# oLoRa-part-MainMCU.net
KiCad netlist of a schematic drawn in EasyEDA
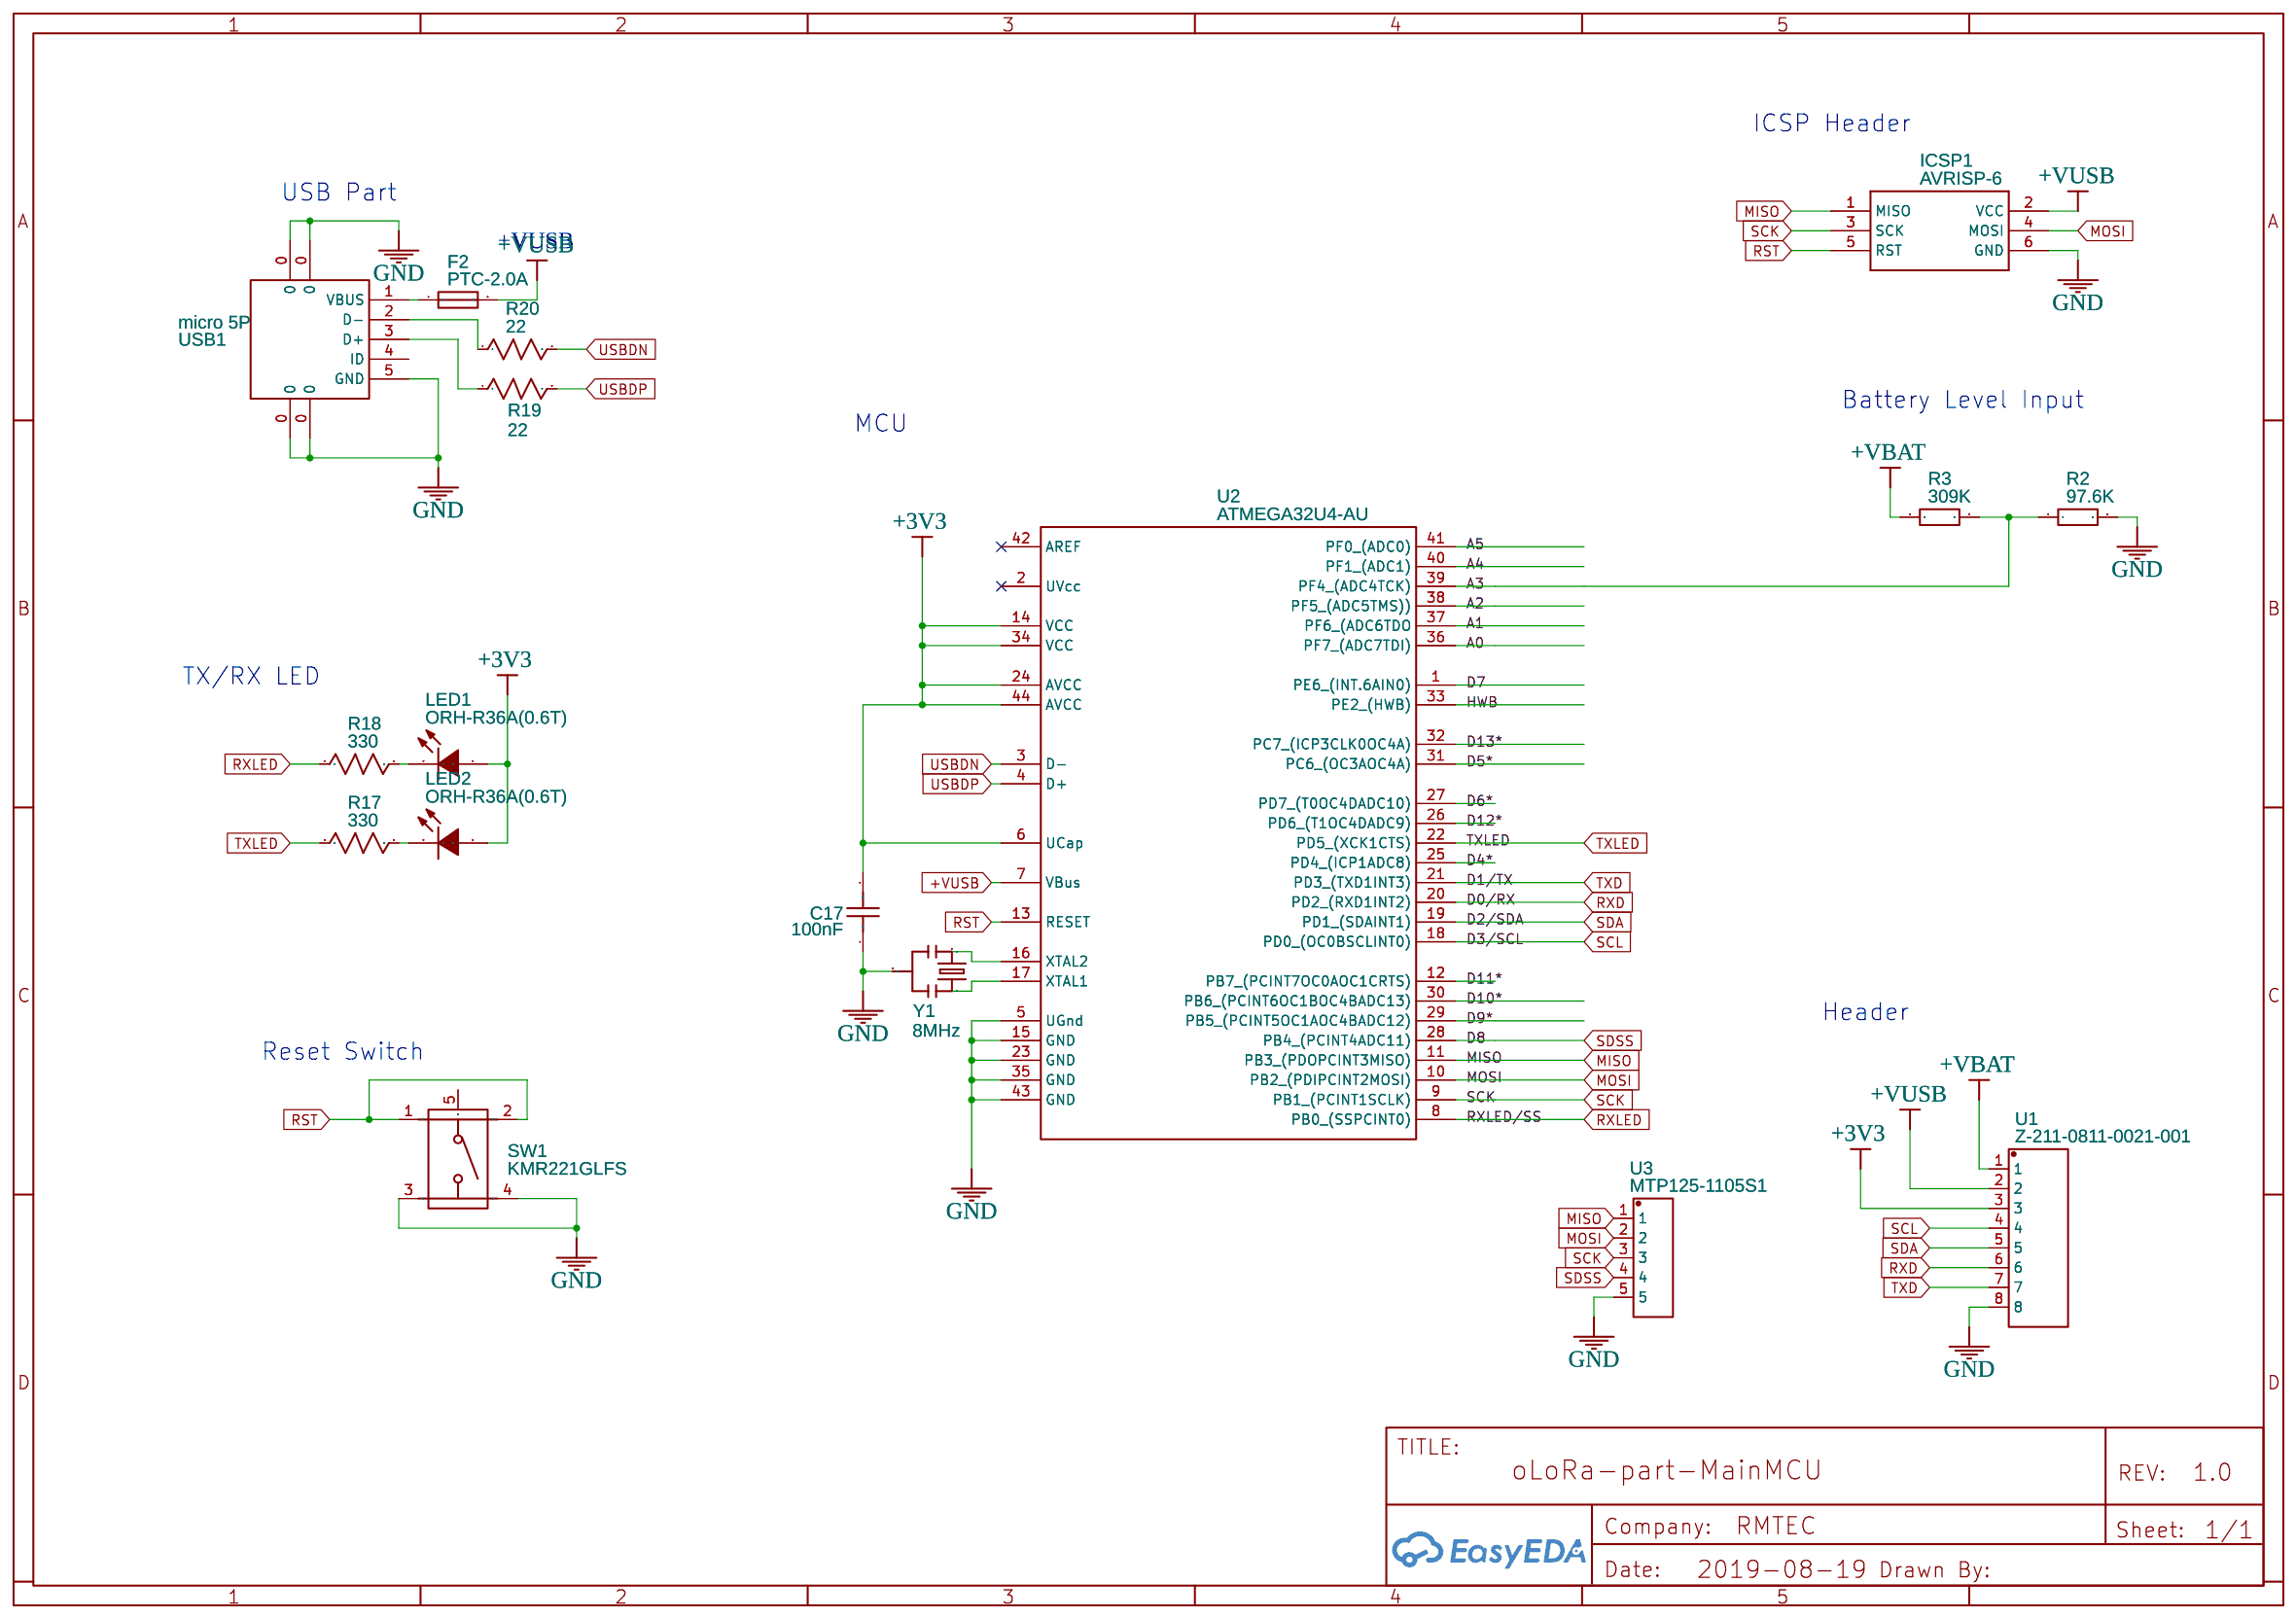
[diagram p0: schematic sheet]

(export (version "E")
  (design (tool "Eeschema 10.0.6"))
  (components
    (comp (ref "C17")
      (value "100nF")
      (fields
        (field (name "BOM_Manufacturer Part") "CC0603KRX7R9BB104")
        (field (name "BOM_Supplier Part") "C14663")
      )
      (libsource (lib "") (part "CC0603KRX7R9BB104"))
    )
    (comp (ref "F2")
      (value "PTC-2.0A")
      (fields
        (field (name "BOM_Manufacturer Part") "MF-MSMF200-2")
        (field (name "BOM_Supplier Part") "C210837")
      )
      (libsource (lib "") (part "Unknown_225_145"))
    )
    (comp (ref "ICSP1")
      (value "AVRISP-6")
      (fields (field (name "BOM_Manufacturer Part") "?"))
      (libsource (lib "") (part "Unknown_970_110"))
    )
    (comp (ref "LED1")
      (value "ORH-R36A(0.6T)")
      (fields (field (name "BOM_Supplier Part") "C205445"))
      (libsource (lib "") (part "Unknown_220_380"))
    )
    (comp (ref "LED2")
      (value "ORH-R36A(0.6T)")
      (fields (field (name "BOM_Supplier Part") "C205445"))
      (libsource (lib "") (part "Unknown_220_420"))
    )
    (comp (ref "R2")
      (value "97.6K")
      (fields
        (field (name "BOM_Manufacturer Part") "CR0603-FX-9762ELF")
        (field (name "BOM_Supplier Part") "C203901")
      )
      (libsource (lib "") (part "CR0603-FX-9762ELF"))
    )
    (comp (ref "R3")
      (value "309K")
      (fields
        (field (name "BOM_Manufacturer Part") "0603WAF3093T5E")
        (field (name "BOM_Supplier Part") "C23001")
      )
      (libsource (lib "") (part "0603WAF3093T5E"))
    )
    (comp (ref "R17") (value "330") (libsource (lib "") (part "Res_0603(1/10W)_US")))
    (comp (ref "R18") (value "330") (libsource (lib "") (part "Res_0603(1/10W)_US")))
    (comp (ref "R19") (value "22") (libsource (lib "") (part "Res_0603(1/10W)_US")))
    (comp (ref "R20") (value "22") (libsource (lib "") (part "Res_0603(1/10W)_US")))
    (comp (ref "SW1")
      (value "KMR221GLFS")
      (fields (field (name "BOM_Supplier Part") "C72443"))
      (libsource (lib "") (part "Unknown_225_575"))
    )
    (comp (ref "U1")
      (value "Z-211-0811-0021-001")
      (fields (field (name "BOM_Supplier Part") "C190820"))
      (libsource (lib "") (part "Unknown_1020_620"))
    )
    (comp (ref "U2")
      (value "ATMEGA32U4-AU")
      (fields (field (name "BOM_Supplier Part") "C44854"))
      (libsource (lib "") (part "Unknown_615_415"))
    )
    (comp (ref "U3")
      (value "MTP125-1105S1")
      (fields (field (name "BOM_Supplier Part") "C358687"))
      (libsource (lib "") (part "Unknown_830_630"))
    )
    (comp (ref "USB1")
      (value "micro 5P")
      (fields (field (name "BOM_Supplier Part") "C77238"))
      (libsource (lib "") (part "Unknown_160_165"))
    )
    (comp (ref "Y1")
      (value "8MHz")
      (fields (field (name "BOM_Manufacturer Part") "CSTCE8M00G55-R0"))
      (libsource (lib "") (part "Unknown_475_485"))
    )
  )
  (nets
    (net (code "1") (name "+3V3") (class "Default")
      (node (ref "C17") (pin "2") (pinfunction "2_2") (pintype "unspecified"))
      (node (ref "LED1") (pin "1") (pinfunction "A_1") (pintype "unspecified"))
      (node (ref "LED2") (pin "1") (pinfunction "A_1") (pintype "unspecified"))
      (node (ref "U1") (pin "3") (pinfunction "3_3") (pintype "unspecified"))
      (node (ref "U2") (pin "14") (pinfunction "VCC_14") (pintype "passive"))
      (node (ref "U2") (pin "24") (pinfunction "AVCC_24") (pintype "passive"))
      (node (ref "U2") (pin "34") (pinfunction "VCC_34") (pintype "passive"))
      (node (ref "U2") (pin "44") (pinfunction "AVCC_44") (pintype "passive"))
      (node (ref "U2") (pin "6") (pinfunction "UCap_6") (pintype "unspecified"))
    )
    (net (code "2") (name "+VBAT") (class "Default")
      (node (ref "R3") (pin "1") (pinfunction "1_1") (pintype "input"))
      (node (ref "U1") (pin "1") (pinfunction "1_1") (pintype "unspecified"))
    )
    (net (code "3") (name "+VUSB") (class "Default")
      (node (ref "F2") (pin "2") (pinfunction "2_2") (pintype "unspecified"))
      (node (ref "ICSP1") (pin "2") (pinfunction "VCC_2") (pintype "passive"))
      (node (ref "U1") (pin "2") (pinfunction "2_2") (pintype "unspecified"))
      (node (ref "U2") (pin "7") (pinfunction "VBus_7") (pintype "unspecified"))
    )
    (net (code "4") (name "/A0") (class "Default")
      (node (ref "U2") (pin "36") (pinfunction "PF7_(ADC7TDI)_36") (pintype "bidirectional"))
    )
    (net (code "5") (name "/A1") (class "Default")
      (node (ref "U2") (pin "37") (pinfunction "PF6_(ADC6TDO_37") (pintype "bidirectional"))
    )
    (net (code "6") (name "/A2") (class "Default")
      (node (ref "U2") (pin "38") (pinfunction "PF5_(ADC5TMS))_38") (pintype "bidirectional"))
    )
    (net (code "7") (name "/A3") (class "Default")
      (node (ref "R2") (pin "1") (pinfunction "1_1") (pintype "unspecified"))
      (node (ref "R3") (pin "2") (pinfunction "2_2") (pintype "input"))
      (node (ref "U2") (pin "39") (pinfunction "PF4_(ADC4TCK)_39") (pintype "bidirectional"))
    )
    (net (code "8") (name "/A4") (class "Default")
      (node (ref "U2") (pin "40") (pinfunction "PF1_(ADC1)_40") (pintype "bidirectional"))
    )
    (net (code "9") (name "/A5") (class "Default")
      (node (ref "U2") (pin "41") (pinfunction "PF0_(ADC0)_41") (pintype "bidirectional"))
    )
    (net (code "10") (name "/D4*") (class "Default")
      (node (ref "U2") (pin "25") (pinfunction "PD4_(ICP1ADC8)_25") (pintype "bidirectional"))
    )
    (net (code "11") (name "/D5*") (class "Default")
      (node (ref "U2") (pin "31") (pinfunction "PC6_(OC3AOC4A)_31") (pintype "bidirectional"))
    )
    (net (code "12") (name "/D6*") (class "Default")
      (node (ref "U2") (pin "27") (pinfunction "PD7_(T0OC4DADC10)_27") (pintype "bidirectional"))
    )
    (net (code "13") (name "/D7") (class "Default")
      (node (ref "U2") (pin "1") (pinfunction "PE6_(INT.6AIN0)_1") (pintype "bidirectional"))
    )
    (net (code "14") (name "/D9*") (class "Default")
      (node (ref "U2") (pin "29") (pinfunction "PB5_(PCINT5OC1AOC4BADC12)_29") (pintype "bidirectional"))
    )
    (net (code "15") (name "/D10*") (class "Default")
      (node (ref "U2") (pin "30") (pinfunction "PB6_(PCINT6OC1BOC4BADC13)_30") (pintype "bidirectional"))
    )
    (net (code "16") (name "/D11*") (class "Default")
      (node (ref "U2") (pin "12") (pinfunction "PB7_(PCINT7OC0AOC1CRTS)_12") (pintype "bidirectional"))
    )
    (net (code "17") (name "/D12*") (class "Default")
      (node (ref "U2") (pin "26") (pinfunction "PD6_(T1OC4DADC9)_26") (pintype "bidirectional"))
    )
    (net (code "18") (name "/D13*") (class "Default")
      (node (ref "U2") (pin "32") (pinfunction "PC7_(ICP3CLK0OC4A)_32") (pintype "bidirectional"))
    )
    (net (code "19") (name "/HWB") (class "Default")
      (node (ref "U2") (pin "33") (pinfunction "PE2_(HWB)_33") (pintype "bidirectional"))
    )
    (net (code "20") (name "GND") (class "Default")
      (node (ref "C17") (pin "1") (pinfunction "1_1") (pintype "unspecified"))
      (node (ref "ICSP1") (pin "6") (pinfunction "GND_6") (pintype "passive"))
      (node (ref "R2") (pin "2") (pinfunction "2_2") (pintype "unspecified"))
      (node (ref "SW1") (pin "3") (pinfunction "3_3") (pintype "unspecified"))
      (node (ref "SW1") (pin "4") (pinfunction "4_4") (pintype "unspecified"))
      (node (ref "U1") (pin "8") (pinfunction "8_8") (pintype "unspecified"))
      (node (ref "U2") (pin "15") (pinfunction "GND_15") (pintype "passive"))
      (node (ref "U2") (pin "23") (pinfunction "GND_23") (pintype "passive"))
      (node (ref "U2") (pin "35") (pinfunction "GND_35") (pintype "passive"))
      (node (ref "U2") (pin "43") (pinfunction "GND_43") (pintype "passive"))
      (node (ref "U2") (pin "5") (pinfunction "UGnd_5") (pintype "passive"))
      (node (ref "U3") (pin "5") (pinfunction "5_5") (pintype "unspecified"))
      (node (ref "USB1") (pin "0") (pinfunction "0_0") (pintype "unspecified"))
      (node (ref "USB1") (pin "5") (pinfunction "GND_5") (pintype "unspecified"))
      (node (ref "Y1") (pin "2") (pinfunction "2_2") (pintype "unspecified"))
    )
    (net (code "21") (name "MISO") (class "Default")
      (node (ref "ICSP1") (pin "1") (pinfunction "MISO_1") (pintype "input"))
      (node (ref "U2") (pin "11") (pinfunction "PB3_(PDOPCINT3MISO)_11") (pintype "bidirectional"))
      (node (ref "U3") (pin "1") (pinfunction "1_1") (pintype "unspecified"))
    )
    (net (code "22") (name "MOSI") (class "Default")
      (node (ref "ICSP1") (pin "4") (pinfunction "MOSI_4") (pintype "output"))
      (node (ref "U2") (pin "10") (pinfunction "PB2_(PDIPCINT2MOSI)_10") (pintype "bidirectional"))
      (node (ref "U3") (pin "2") (pinfunction "2_2") (pintype "unspecified"))
    )
    (net (code "23") (name "Net-(LED1-K)") (class "Default")
      (node (ref "LED1") (pin "2") (pinfunction "K_2") (pintype "unspecified"))
      (node (ref "R18") (pin "2") (pinfunction "2_2") (pintype "unspecified"))
    )
    (net (code "24") (name "Net-(LED2-K)") (class "Default")
      (node (ref "LED2") (pin "2") (pinfunction "K_2") (pintype "unspecified"))
      (node (ref "R17") (pin "2") (pinfunction "2_2") (pintype "unspecified"))
    )
    (net (code "25") (name "Net-(U2-XTAL1)") (class "Default")
      (node (ref "U2") (pin "17") (pinfunction "XTAL1_17") (pintype "unspecified"))
      (node (ref "Y1") (pin "3") (pinfunction "3_3") (pintype "unspecified"))
    )
    (net (code "26") (name "Net-(U2-XTAL2)") (class "Default")
      (node (ref "U2") (pin "16") (pinfunction "XTAL2_16") (pintype "output"))
      (node (ref "Y1") (pin "1") (pinfunction "1_1") (pintype "unspecified"))
    )
    (net (code "27") (name "Net-(USB1-D+)") (class "Default")
      (node (ref "R19") (pin "1") (pinfunction "1_1") (pintype "unspecified"))
      (node (ref "USB1") (pin "3") (pinfunction "D+_3") (pintype "unspecified"))
    )
    (net (code "28") (name "Net-(USB1-D-)") (class "Default")
      (node (ref "R20") (pin "1") (pinfunction "1_1") (pintype "unspecified"))
      (node (ref "USB1") (pin "2") (pinfunction "D-_2") (pintype "unspecified"))
    )
    (net (code "29") (name "Net-(USB1-VBUS)") (class "Default")
      (node (ref "F2") (pin "1") (pinfunction "1_1") (pintype "unspecified"))
      (node (ref "USB1") (pin "1") (pinfunction "VBUS_1") (pintype "unspecified"))
    )
    (net (code "30") (name "RST") (class "Default")
      (node (ref "ICSP1") (pin "5") (pinfunction "RST_5") (pintype "output"))
      (node (ref "SW1") (pin "1") (pinfunction "1_1") (pintype "unspecified"))
      (node (ref "SW1") (pin "2") (pinfunction "2_2") (pintype "unspecified"))
      (node (ref "U2") (pin "13") (pinfunction "RESET_13") (pintype "unspecified"))
    )
    (net (code "31") (name "RXD") (class "Default")
      (node (ref "U1") (pin "6") (pinfunction "6_6") (pintype "unspecified"))
      (node (ref "U2") (pin "20") (pinfunction "PD2_(RXD1INT2)_20") (pintype "bidirectional"))
    )
    (net (code "32") (name "RXLED") (class "Default")
      (node (ref "R18") (pin "1") (pinfunction "1_1") (pintype "unspecified"))
      (node (ref "U2") (pin "8") (pinfunction "PB0_(SSPCINT0)_8") (pintype "bidirectional"))
    )
    (net (code "33") (name "SCK") (class "Default")
      (node (ref "ICSP1") (pin "3") (pinfunction "SCK_3") (pintype "output"))
      (node (ref "U2") (pin "9") (pinfunction "PB1_(PCINT1SCLK)_9") (pintype "bidirectional"))
      (node (ref "U3") (pin "3") (pinfunction "3_3") (pintype "unspecified"))
    )
    (net (code "34") (name "SCL") (class "Default")
      (node (ref "U1") (pin "4") (pinfunction "4_4") (pintype "unspecified"))
      (node (ref "U2") (pin "18") (pinfunction "PD0_(OC0BSCLINT0)_18") (pintype "bidirectional"))
    )
    (net (code "35") (name "SDA") (class "Default")
      (node (ref "U1") (pin "5") (pinfunction "5_5") (pintype "unspecified"))
      (node (ref "U2") (pin "19") (pinfunction "PD1_(SDAINT1)_19") (pintype "bidirectional"))
    )
    (net (code "36") (name "SDSS") (class "Default")
      (node (ref "U2") (pin "28") (pinfunction "PB4_(PCINT4ADC11)_28") (pintype "bidirectional"))
      (node (ref "U3") (pin "4") (pinfunction "4_4") (pintype "unspecified"))
    )
    (net (code "37") (name "TXD") (class "Default")
      (node (ref "U1") (pin "7") (pinfunction "7_7") (pintype "unspecified"))
      (node (ref "U2") (pin "21") (pinfunction "PD3_(TXD1INT3)_21") (pintype "bidirectional"))
    )
    (net (code "38") (name "TXLED") (class "Default")
      (node (ref "R17") (pin "1") (pinfunction "1_1") (pintype "unspecified"))
      (node (ref "U2") (pin "22") (pinfunction "PD5_(XCK1CTS)_22") (pintype "bidirectional"))
    )
    (net (code "39") (name "USBDN") (class "Default")
      (node (ref "R20") (pin "2") (pinfunction "2_2") (pintype "unspecified"))
      (node (ref "U2") (pin "3") (pinfunction "D-_3") (pintype "bidirectional"))
    )
    (net (code "40") (name "USBDP") (class "Default")
      (node (ref "R19") (pin "2") (pinfunction "2_2") (pintype "unspecified"))
      (node (ref "U2") (pin "4") (pinfunction "D+_4") (pintype "bidirectional"))
    )
    (net (code "41") (name "unconnected-(SW1-Pad5)") (class "Default")
      (node (ref "SW1") (pin "5") (pinfunction "5_5") (pintype "unspecified"))
    )
    (net (code "42") (name "unconnected-(U2-AREF-Pad42)") (class "Default")
      (node (ref "U2") (pin "42") (pinfunction "AREF_42") (pintype "unspecified+no_connect"))
    )
    (net (code "43") (name "unconnected-(U2-UVcc-Pad2)") (class "Default")
      (node (ref "U2") (pin "2") (pinfunction "UVcc_2") (pintype "passive+no_connect"))
    )
    (net (code "44") (name "unconnected-(USB1-ID-Pad4)") (class "Default")
      (node (ref "USB1") (pin "4") (pinfunction "ID_4") (pintype "unspecified"))
    )
  )
)
